# LED_String_AREM-80C0.net
KiCad netlist of a schematic drawn in Altium Designer
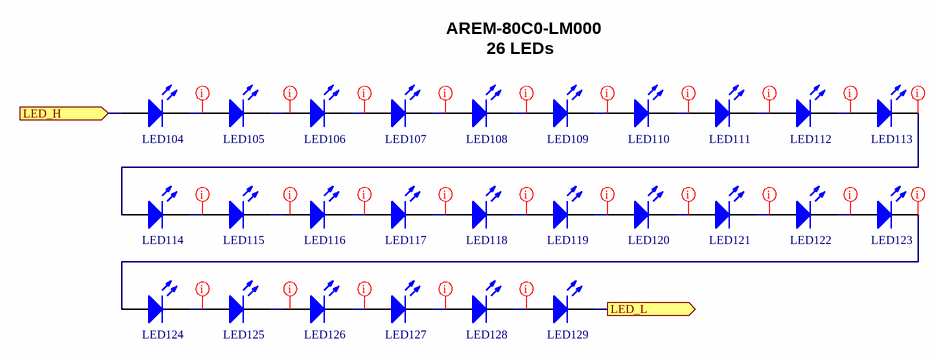
[diagram p0: LED_String_AREM-80C0.SchDoc]

(export (version "E")
  (design (tool "Eeschema 10.0.6"))
  (components
    (comp (ref "LED104")
      (value "AREM-80C0-LM000")
      (footprint "AREM-80C0-LM000")
      (description "Infrared (IR) Emitter 850nm 1.5V 70mA 14.4mW/sr @ 70mA (Typ) 120° 2-PLCC")
      (fields (field (name "MFR") "Broadcom Limited") (field (name "MANUFACTURER") "Broadcom"))
      (libsource (lib "ETHZ Vault") (part "LED"))
    )
    (comp (ref "LED105")
      (value "AREM-80C0-LM000")
      (footprint "AREM-80C0-LM000")
      (description "Infrared (IR) Emitter 850nm 1.5V 70mA 14.4mW/sr @ 70mA (Typ) 120° 2-PLCC")
      (fields (field (name "MFR") "Broadcom Limited") (field (name "MANUFACTURER") "Broadcom"))
      (libsource (lib "ETHZ Vault") (part "LED"))
    )
    (comp (ref "LED106")
      (value "AREM-80C0-LM000")
      (footprint "AREM-80C0-LM000")
      (description "Infrared (IR) Emitter 850nm 1.5V 70mA 14.4mW/sr @ 70mA (Typ) 120° 2-PLCC")
      (fields (field (name "MFR") "Broadcom Limited") (field (name "MANUFACTURER") "Broadcom"))
      (libsource (lib "ETHZ Vault") (part "LED"))
    )
    (comp (ref "LED107")
      (value "AREM-80C0-LM000")
      (footprint "AREM-80C0-LM000")
      (description "Infrared (IR) Emitter 850nm 1.5V 70mA 14.4mW/sr @ 70mA (Typ) 120° 2-PLCC")
      (fields (field (name "MFR") "Broadcom Limited") (field (name "MANUFACTURER") "Broadcom"))
      (libsource (lib "ETHZ Vault") (part "LED"))
    )
    (comp (ref "LED108")
      (value "AREM-80C0-LM000")
      (footprint "AREM-80C0-LM000")
      (description "Infrared (IR) Emitter 850nm 1.5V 70mA 14.4mW/sr @ 70mA (Typ) 120° 2-PLCC")
      (fields (field (name "MFR") "Broadcom Limited") (field (name "MANUFACTURER") "Broadcom"))
      (libsource (lib "ETHZ Vault") (part "LED"))
    )
    (comp (ref "LED109")
      (value "AREM-80C0-LM000")
      (footprint "AREM-80C0-LM000")
      (description "Infrared (IR) Emitter 850nm 1.5V 70mA 14.4mW/sr @ 70mA (Typ) 120° 2-PLCC")
      (fields (field (name "MFR") "Broadcom Limited") (field (name "MANUFACTURER") "Broadcom"))
      (libsource (lib "ETHZ Vault") (part "LED"))
    )
    (comp (ref "LED110")
      (value "AREM-80C0-LM000")
      (footprint "AREM-80C0-LM000")
      (description "Infrared (IR) Emitter 850nm 1.5V 70mA 14.4mW/sr @ 70mA (Typ) 120° 2-PLCC")
      (fields (field (name "MFR") "Broadcom Limited") (field (name "MANUFACTURER") "Broadcom"))
      (libsource (lib "ETHZ Vault") (part "LED"))
    )
    (comp (ref "LED111")
      (value "AREM-80C0-LM000")
      (footprint "AREM-80C0-LM000")
      (description "Infrared (IR) Emitter 850nm 1.5V 70mA 14.4mW/sr @ 70mA (Typ) 120° 2-PLCC")
      (fields (field (name "MFR") "Broadcom Limited") (field (name "MANUFACTURER") "Broadcom"))
      (libsource (lib "ETHZ Vault") (part "LED"))
    )
    (comp (ref "LED112")
      (value "AREM-80C0-LM000")
      (footprint "AREM-80C0-LM000")
      (description "Infrared (IR) Emitter 850nm 1.5V 70mA 14.4mW/sr @ 70mA (Typ) 120° 2-PLCC")
      (fields (field (name "MFR") "Broadcom Limited") (field (name "MANUFACTURER") "Broadcom"))
      (libsource (lib "ETHZ Vault") (part "LED"))
    )
    (comp (ref "LED113")
      (value "AREM-80C0-LM000")
      (footprint "AREM-80C0-LM000")
      (description "Infrared (IR) Emitter 850nm 1.5V 70mA 14.4mW/sr @ 70mA (Typ) 120° 2-PLCC")
      (fields (field (name "MFR") "Broadcom Limited") (field (name "MANUFACTURER") "Broadcom"))
      (libsource (lib "ETHZ Vault") (part "LED"))
    )
    (comp (ref "LED114")
      (value "AREM-80C0-LM000")
      (footprint "AREM-80C0-LM000")
      (description "Infrared (IR) Emitter 850nm 1.5V 70mA 14.4mW/sr @ 70mA (Typ) 120° 2-PLCC")
      (fields (field (name "MFR") "Broadcom Limited") (field (name "MANUFACTURER") "Broadcom"))
      (libsource (lib "ETHZ Vault") (part "LED"))
    )
    (comp (ref "LED115")
      (value "AREM-80C0-LM000")
      (footprint "AREM-80C0-LM000")
      (description "Infrared (IR) Emitter 850nm 1.5V 70mA 14.4mW/sr @ 70mA (Typ) 120° 2-PLCC")
      (fields (field (name "MFR") "Broadcom Limited") (field (name "MANUFACTURER") "Broadcom"))
      (libsource (lib "ETHZ Vault") (part "LED"))
    )
    (comp (ref "LED116")
      (value "AREM-80C0-LM000")
      (footprint "AREM-80C0-LM000")
      (description "Infrared (IR) Emitter 850nm 1.5V 70mA 14.4mW/sr @ 70mA (Typ) 120° 2-PLCC")
      (fields (field (name "MFR") "Broadcom Limited") (field (name "MANUFACTURER") "Broadcom"))
      (libsource (lib "ETHZ Vault") (part "LED"))
    )
    (comp (ref "LED117")
      (value "AREM-80C0-LM000")
      (footprint "AREM-80C0-LM000")
      (description "Infrared (IR) Emitter 850nm 1.5V 70mA 14.4mW/sr @ 70mA (Typ) 120° 2-PLCC")
      (fields (field (name "MFR") "Broadcom Limited") (field (name "MANUFACTURER") "Broadcom"))
      (libsource (lib "ETHZ Vault") (part "LED"))
    )
    (comp (ref "LED118")
      (value "AREM-80C0-LM000")
      (footprint "AREM-80C0-LM000")
      (description "Infrared (IR) Emitter 850nm 1.5V 70mA 14.4mW/sr @ 70mA (Typ) 120° 2-PLCC")
      (fields (field (name "MFR") "Broadcom Limited") (field (name "MANUFACTURER") "Broadcom"))
      (libsource (lib "ETHZ Vault") (part "LED"))
    )
    (comp (ref "LED119")
      (value "AREM-80C0-LM000")
      (footprint "AREM-80C0-LM000")
      (description "Infrared (IR) Emitter 850nm 1.5V 70mA 14.4mW/sr @ 70mA (Typ) 120° 2-PLCC")
      (fields (field (name "MFR") "Broadcom Limited") (field (name "MANUFACTURER") "Broadcom"))
      (libsource (lib "ETHZ Vault") (part "LED"))
    )
    (comp (ref "LED120")
      (value "AREM-80C0-LM000")
      (footprint "AREM-80C0-LM000")
      (description "Infrared (IR) Emitter 850nm 1.5V 70mA 14.4mW/sr @ 70mA (Typ) 120° 2-PLCC")
      (fields (field (name "MFR") "Broadcom Limited") (field (name "MANUFACTURER") "Broadcom"))
      (libsource (lib "ETHZ Vault") (part "LED"))
    )
    (comp (ref "LED121")
      (value "AREM-80C0-LM000")
      (footprint "AREM-80C0-LM000")
      (description "Infrared (IR) Emitter 850nm 1.5V 70mA 14.4mW/sr @ 70mA (Typ) 120° 2-PLCC")
      (fields (field (name "MFR") "Broadcom Limited") (field (name "MANUFACTURER") "Broadcom"))
      (libsource (lib "ETHZ Vault") (part "LED"))
    )
    (comp (ref "LED122")
      (value "AREM-80C0-LM000")
      (footprint "AREM-80C0-LM000")
      (description "Infrared (IR) Emitter 850nm 1.5V 70mA 14.4mW/sr @ 70mA (Typ) 120° 2-PLCC")
      (fields (field (name "MFR") "Broadcom Limited") (field (name "MANUFACTURER") "Broadcom"))
      (libsource (lib "ETHZ Vault") (part "LED"))
    )
    (comp (ref "LED123")
      (value "AREM-80C0-LM000")
      (footprint "AREM-80C0-LM000")
      (description "Infrared (IR) Emitter 850nm 1.5V 70mA 14.4mW/sr @ 70mA (Typ) 120° 2-PLCC")
      (fields (field (name "MFR") "Broadcom Limited") (field (name "MANUFACTURER") "Broadcom"))
      (libsource (lib "ETHZ Vault") (part "LED"))
    )
    (comp (ref "LED124")
      (value "AREM-80C0-LM000")
      (footprint "AREM-80C0-LM000")
      (description "Infrared (IR) Emitter 850nm 1.5V 70mA 14.4mW/sr @ 70mA (Typ) 120° 2-PLCC")
      (fields (field (name "MFR") "Broadcom Limited") (field (name "MANUFACTURER") "Broadcom"))
      (libsource (lib "ETHZ Vault") (part "LED"))
    )
    (comp (ref "LED125")
      (value "AREM-80C0-LM000")
      (footprint "AREM-80C0-LM000")
      (description "Infrared (IR) Emitter 850nm 1.5V 70mA 14.4mW/sr @ 70mA (Typ) 120° 2-PLCC")
      (fields (field (name "MFR") "Broadcom Limited") (field (name "MANUFACTURER") "Broadcom"))
      (libsource (lib "ETHZ Vault") (part "LED"))
    )
    (comp (ref "LED126")
      (value "AREM-80C0-LM000")
      (footprint "AREM-80C0-LM000")
      (description "Infrared (IR) Emitter 850nm 1.5V 70mA 14.4mW/sr @ 70mA (Typ) 120° 2-PLCC")
      (fields (field (name "MFR") "Broadcom Limited") (field (name "MANUFACTURER") "Broadcom"))
      (libsource (lib "ETHZ Vault") (part "LED"))
    )
    (comp (ref "LED127")
      (value "AREM-80C0-LM000")
      (footprint "AREM-80C0-LM000")
      (description "Infrared (IR) Emitter 850nm 1.5V 70mA 14.4mW/sr @ 70mA (Typ) 120° 2-PLCC")
      (fields (field (name "MFR") "Broadcom Limited") (field (name "MANUFACTURER") "Broadcom"))
      (libsource (lib "ETHZ Vault") (part "LED"))
    )
    (comp (ref "LED128")
      (value "AREM-80C0-LM000")
      (footprint "AREM-80C0-LM000")
      (description "Infrared (IR) Emitter 850nm 1.5V 70mA 14.4mW/sr @ 70mA (Typ) 120° 2-PLCC")
      (fields (field (name "MFR") "Broadcom Limited") (field (name "MANUFACTURER") "Broadcom"))
      (libsource (lib "ETHZ Vault") (part "LED"))
    )
    (comp (ref "LED129")
      (value "AREM-80C0-LM000")
      (footprint "AREM-80C0-LM000")
      (description "Infrared (IR) Emitter 850nm 1.5V 70mA 14.4mW/sr @ 70mA (Typ) 120° 2-PLCC")
      (fields (field (name "MFR") "Broadcom Limited") (field (name "MANUFACTURER") "Broadcom"))
      (libsource (lib "ETHZ Vault") (part "LED"))
    )
  )
  (nets
    (net (code "1") (name "/LED_H") (class "Default")
      (node (ref "LED104") (pin "2") (pinfunction "A_2") (pintype "passive"))
    )
    (net (code "2") (name "/LED_L") (class "Default")
      (node (ref "LED129") (pin "1") (pinfunction "K_1") (pintype "passive"))
    )
    (net (code "3") (name "Net-(LED104-K)") (class "Default")
      (node (ref "LED104") (pin "1") (pinfunction "K_1") (pintype "passive"))
      (node (ref "LED105") (pin "2") (pinfunction "A_2") (pintype "passive"))
    )
    (net (code "4") (name "Net-(LED105-K)") (class "Default")
      (node (ref "LED105") (pin "1") (pinfunction "K_1") (pintype "passive"))
      (node (ref "LED106") (pin "2") (pinfunction "A_2") (pintype "passive"))
    )
    (net (code "5") (name "Net-(LED106-K)") (class "Default")
      (node (ref "LED106") (pin "1") (pinfunction "K_1") (pintype "passive"))
      (node (ref "LED107") (pin "2") (pinfunction "A_2") (pintype "passive"))
    )
    (net (code "6") (name "Net-(LED107-K)") (class "Default")
      (node (ref "LED107") (pin "1") (pinfunction "K_1") (pintype "passive"))
      (node (ref "LED108") (pin "2") (pinfunction "A_2") (pintype "passive"))
    )
    (net (code "7") (name "Net-(LED108-K)") (class "Default")
      (node (ref "LED108") (pin "1") (pinfunction "K_1") (pintype "passive"))
      (node (ref "LED109") (pin "2") (pinfunction "A_2") (pintype "passive"))
    )
    (net (code "8") (name "Net-(LED109-K)") (class "Default")
      (node (ref "LED109") (pin "1") (pinfunction "K_1") (pintype "passive"))
      (node (ref "LED110") (pin "2") (pinfunction "A_2") (pintype "passive"))
    )
    (net (code "9") (name "Net-(LED110-K)") (class "Default")
      (node (ref "LED110") (pin "1") (pinfunction "K_1") (pintype "passive"))
      (node (ref "LED111") (pin "2") (pinfunction "A_2") (pintype "passive"))
    )
    (net (code "10") (name "Net-(LED111-K)") (class "Default")
      (node (ref "LED111") (pin "1") (pinfunction "K_1") (pintype "passive"))
      (node (ref "LED112") (pin "2") (pinfunction "A_2") (pintype "passive"))
    )
    (net (code "11") (name "Net-(LED112-K)") (class "Default")
      (node (ref "LED112") (pin "1") (pinfunction "K_1") (pintype "passive"))
      (node (ref "LED113") (pin "2") (pinfunction "A_2") (pintype "passive"))
    )
    (net (code "12") (name "Net-(LED113-K)") (class "Default")
      (node (ref "LED113") (pin "1") (pinfunction "K_1") (pintype "passive"))
      (node (ref "LED114") (pin "2") (pinfunction "A_2") (pintype "passive"))
    )
    (net (code "13") (name "Net-(LED114-K)") (class "Default")
      (node (ref "LED114") (pin "1") (pinfunction "K_1") (pintype "passive"))
      (node (ref "LED115") (pin "2") (pinfunction "A_2") (pintype "passive"))
    )
    (net (code "14") (name "Net-(LED115-K)") (class "Default")
      (node (ref "LED115") (pin "1") (pinfunction "K_1") (pintype "passive"))
      (node (ref "LED116") (pin "2") (pinfunction "A_2") (pintype "passive"))
    )
    (net (code "15") (name "Net-(LED116-K)") (class "Default")
      (node (ref "LED116") (pin "1") (pinfunction "K_1") (pintype "passive"))
      (node (ref "LED117") (pin "2") (pinfunction "A_2") (pintype "passive"))
    )
    (net (code "16") (name "Net-(LED117-K)") (class "Default")
      (node (ref "LED117") (pin "1") (pinfunction "K_1") (pintype "passive"))
      (node (ref "LED118") (pin "2") (pinfunction "A_2") (pintype "passive"))
    )
    (net (code "17") (name "Net-(LED118-K)") (class "Default")
      (node (ref "LED118") (pin "1") (pinfunction "K_1") (pintype "passive"))
      (node (ref "LED119") (pin "2") (pinfunction "A_2") (pintype "passive"))
    )
    (net (code "18") (name "Net-(LED119-K)") (class "Default")
      (node (ref "LED119") (pin "1") (pinfunction "K_1") (pintype "passive"))
      (node (ref "LED120") (pin "2") (pinfunction "A_2") (pintype "passive"))
    )
    (net (code "19") (name "Net-(LED120-K)") (class "Default")
      (node (ref "LED120") (pin "1") (pinfunction "K_1") (pintype "passive"))
      (node (ref "LED121") (pin "2") (pinfunction "A_2") (pintype "passive"))
    )
    (net (code "20") (name "Net-(LED121-K)") (class "Default")
      (node (ref "LED121") (pin "1") (pinfunction "K_1") (pintype "passive"))
      (node (ref "LED122") (pin "2") (pinfunction "A_2") (pintype "passive"))
    )
    (net (code "21") (name "Net-(LED122-K)") (class "Default")
      (node (ref "LED122") (pin "1") (pinfunction "K_1") (pintype "passive"))
      (node (ref "LED123") (pin "2") (pinfunction "A_2") (pintype "passive"))
    )
    (net (code "22") (name "Net-(LED123-K)") (class "Default")
      (node (ref "LED123") (pin "1") (pinfunction "K_1") (pintype "passive"))
      (node (ref "LED124") (pin "2") (pinfunction "A_2") (pintype "passive"))
    )
    (net (code "23") (name "Net-(LED124-K)") (class "Default")
      (node (ref "LED124") (pin "1") (pinfunction "K_1") (pintype "passive"))
      (node (ref "LED125") (pin "2") (pinfunction "A_2") (pintype "passive"))
    )
    (net (code "24") (name "Net-(LED125-K)") (class "Default")
      (node (ref "LED125") (pin "1") (pinfunction "K_1") (pintype "passive"))
      (node (ref "LED126") (pin "2") (pinfunction "A_2") (pintype "passive"))
    )
    (net (code "25") (name "Net-(LED126-K)") (class "Default")
      (node (ref "LED126") (pin "1") (pinfunction "K_1") (pintype "passive"))
      (node (ref "LED127") (pin "2") (pinfunction "A_2") (pintype "passive"))
    )
    (net (code "26") (name "Net-(LED127-K)") (class "Default")
      (node (ref "LED127") (pin "1") (pinfunction "K_1") (pintype "passive"))
      (node (ref "LED128") (pin "2") (pinfunction "A_2") (pintype "passive"))
    )
    (net (code "27") (name "Net-(LED128-K)") (class "Default")
      (node (ref "LED128") (pin "1") (pinfunction "K_1") (pintype "passive"))
      (node (ref "LED129") (pin "2") (pinfunction "A_2") (pintype "passive"))
    )
  )
)
